# I2C16RJ45.net
KiCad netlist of a schematic drawn in EAGLE
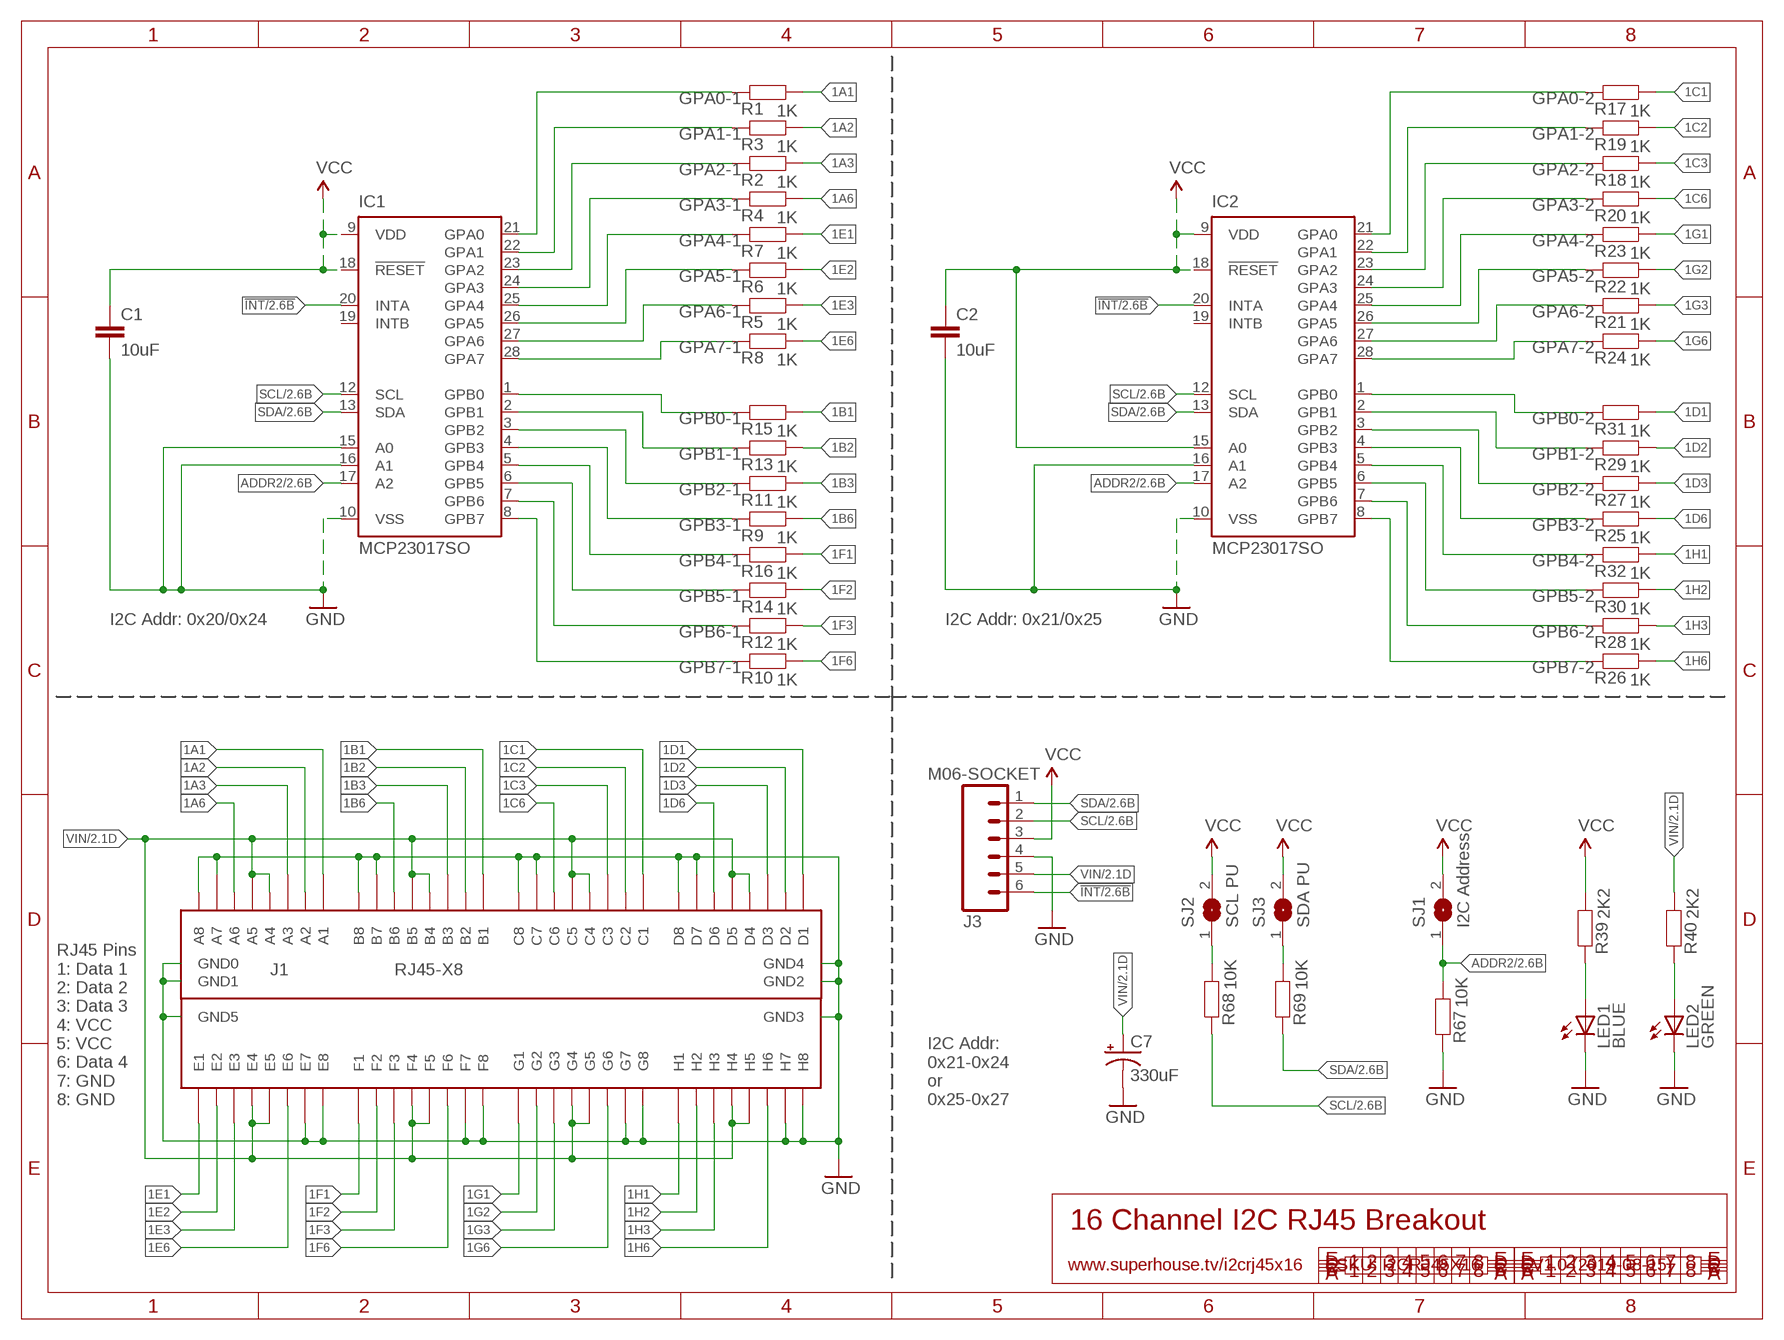
[diagram p0: schematic, sheet 1]
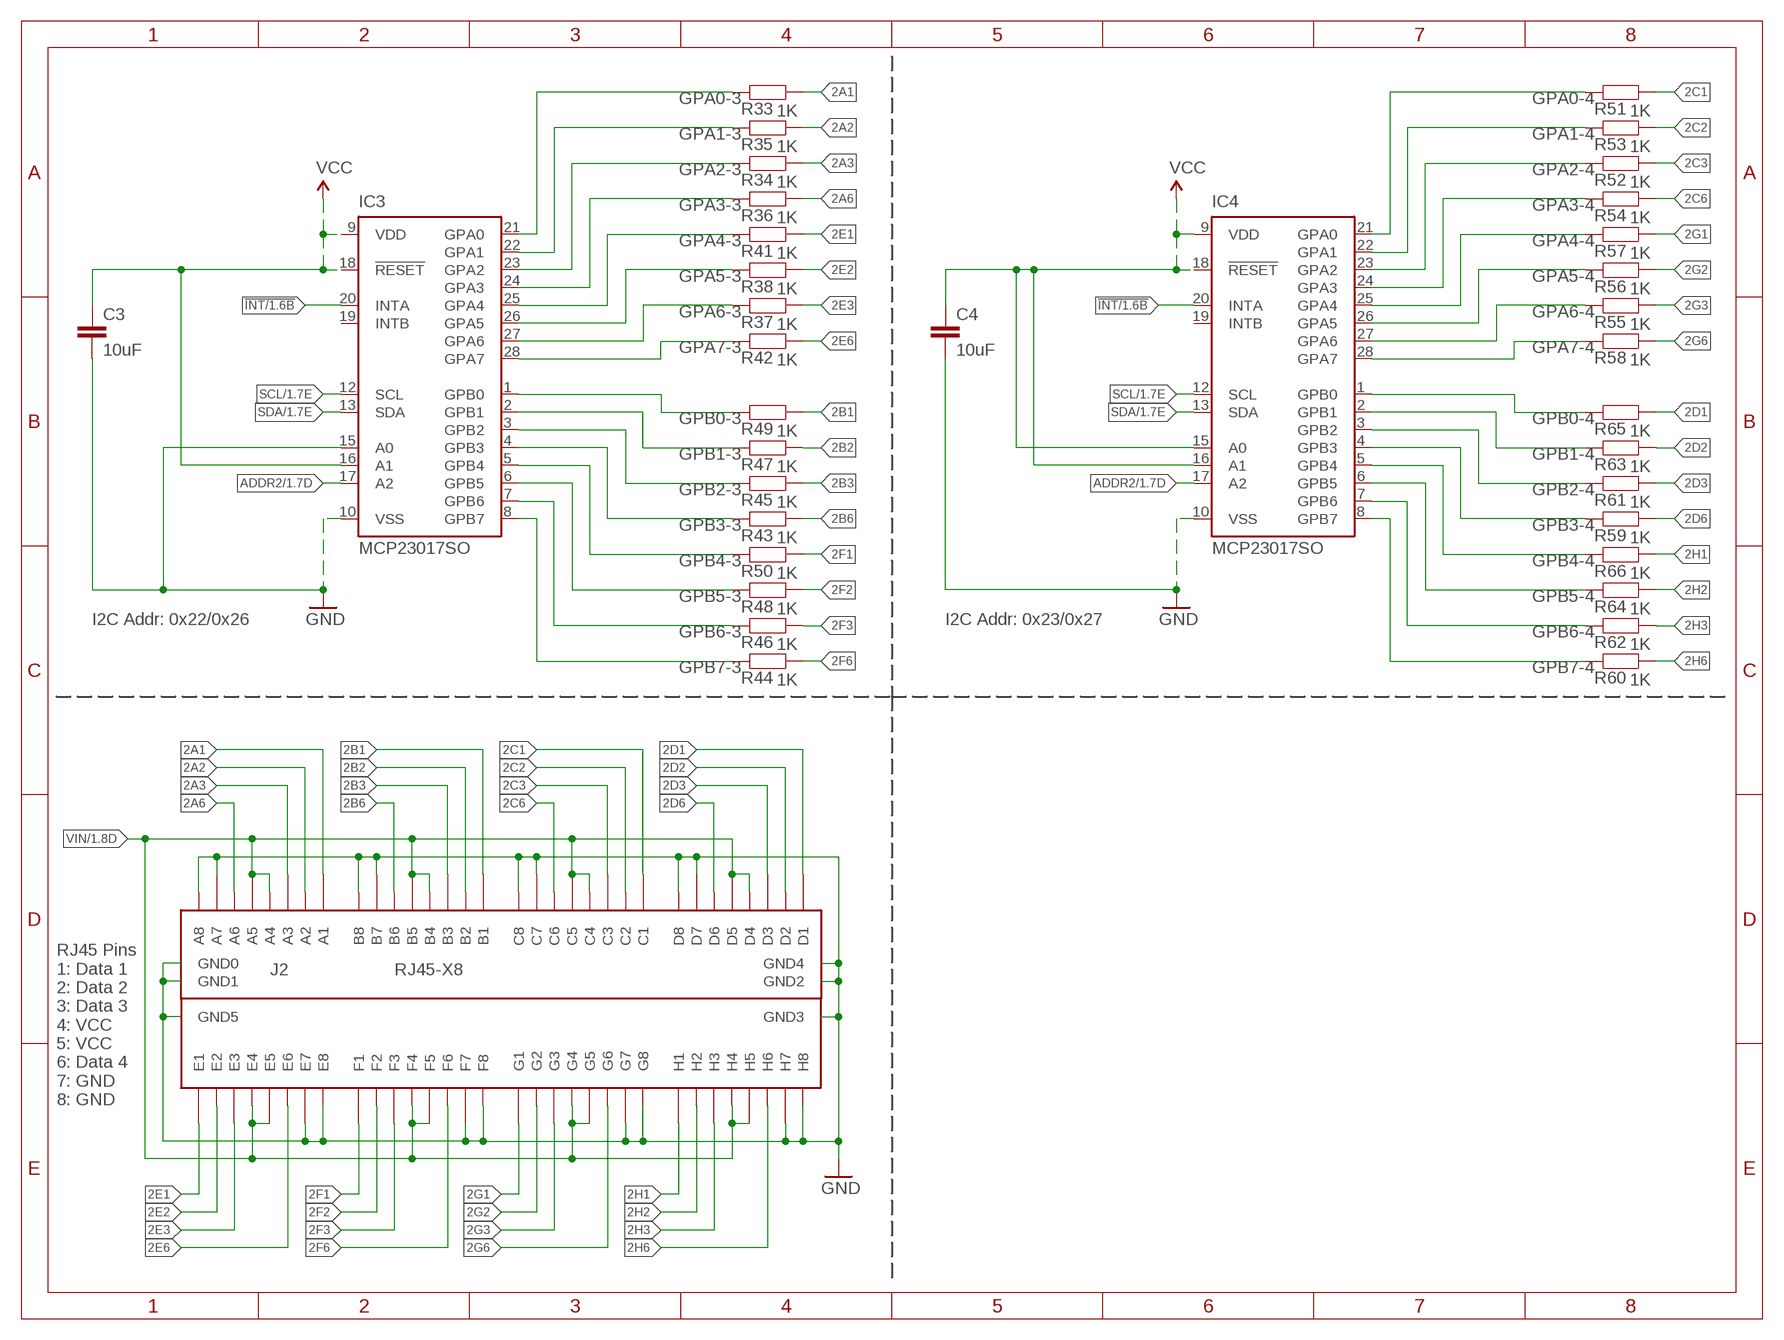
[diagram p1: schematic, sheet 2]

(export (version "E")
  (design (tool "Eeschema 10.0.6"))
  (components
    (comp (ref "C3")
      (value "10uF")
      (footprint "eagle-import:C0805")
      (libsource (lib "eagle-import") (part "CAP0805"))
    )
    (comp (ref "C4")
      (value "10uF")
      (footprint "eagle-import:C0805")
      (libsource (lib "eagle-import") (part "CAP0805"))
    )
    (comp (ref "IC3")
      (value "MCP23017SO")
      (footprint "eagle-import:SO28W")
      (libsource (lib "eagle-import") (part "MCP23017SO"))
    )
    (comp (ref "IC4")
      (value "MCP23017SO")
      (footprint "eagle-import:SO28W")
      (libsource (lib "eagle-import") (part "MCP23017SO"))
    )
    (comp (ref "J2")
      (value "RJ45-X8")
      (footprint "eagle-import:RJ45-2X4")
      (libsource (lib "eagle-import") (part "RJ45-X8"))
    )
    (comp (ref "R33")
      (value "1K")
      (footprint "eagle-import:R0603")
      (libsource (lib "eagle-import") (part "RESISTOR0603"))
    )
    (comp (ref "R34")
      (value "1K")
      (footprint "eagle-import:R0603")
      (libsource (lib "eagle-import") (part "RESISTOR0603"))
    )
    (comp (ref "R35")
      (value "1K")
      (footprint "eagle-import:R0603")
      (libsource (lib "eagle-import") (part "RESISTOR0603"))
    )
    (comp (ref "R36")
      (value "1K")
      (footprint "eagle-import:R0603")
      (libsource (lib "eagle-import") (part "RESISTOR0603"))
    )
    (comp (ref "R37")
      (value "1K")
      (footprint "eagle-import:R0603")
      (libsource (lib "eagle-import") (part "RESISTOR0603"))
    )
    (comp (ref "R38")
      (value "1K")
      (footprint "eagle-import:R0603")
      (libsource (lib "eagle-import") (part "RESISTOR0603"))
    )
    (comp (ref "R41")
      (value "1K")
      (footprint "eagle-import:R0603")
      (libsource (lib "eagle-import") (part "RESISTOR0603"))
    )
    (comp (ref "R42")
      (value "1K")
      (footprint "eagle-import:R0603")
      (libsource (lib "eagle-import") (part "RESISTOR0603"))
    )
    (comp (ref "R43")
      (value "1K")
      (footprint "eagle-import:R0603")
      (libsource (lib "eagle-import") (part "RESISTOR0603"))
    )
    (comp (ref "R44")
      (value "1K")
      (footprint "eagle-import:R0603")
      (libsource (lib "eagle-import") (part "RESISTOR0603"))
    )
    (comp (ref "R45")
      (value "1K")
      (footprint "eagle-import:R0603")
      (libsource (lib "eagle-import") (part "RESISTOR0603"))
    )
    (comp (ref "R46")
      (value "1K")
      (footprint "eagle-import:R0603")
      (libsource (lib "eagle-import") (part "RESISTOR0603"))
    )
    (comp (ref "R47")
      (value "1K")
      (footprint "eagle-import:R0603")
      (libsource (lib "eagle-import") (part "RESISTOR0603"))
    )
    (comp (ref "R48")
      (value "1K")
      (footprint "eagle-import:R0603")
      (libsource (lib "eagle-import") (part "RESISTOR0603"))
    )
    (comp (ref "R49")
      (value "1K")
      (footprint "eagle-import:R0603")
      (libsource (lib "eagle-import") (part "RESISTOR0603"))
    )
    (comp (ref "R50")
      (value "1K")
      (footprint "eagle-import:R0603")
      (libsource (lib "eagle-import") (part "RESISTOR0603"))
    )
    (comp (ref "R51")
      (value "1K")
      (footprint "eagle-import:R0603")
      (libsource (lib "eagle-import") (part "RESISTOR0603"))
    )
    (comp (ref "R52")
      (value "1K")
      (footprint "eagle-import:R0603")
      (libsource (lib "eagle-import") (part "RESISTOR0603"))
    )
    (comp (ref "R53")
      (value "1K")
      (footprint "eagle-import:R0603")
      (libsource (lib "eagle-import") (part "RESISTOR0603"))
    )
    (comp (ref "R54")
      (value "1K")
      (footprint "eagle-import:R0603")
      (libsource (lib "eagle-import") (part "RESISTOR0603"))
    )
    (comp (ref "R55")
      (value "1K")
      (footprint "eagle-import:R0603")
      (libsource (lib "eagle-import") (part "RESISTOR0603"))
    )
    (comp (ref "R56")
      (value "1K")
      (footprint "eagle-import:R0603")
      (libsource (lib "eagle-import") (part "RESISTOR0603"))
    )
    (comp (ref "R57")
      (value "1K")
      (footprint "eagle-import:R0603")
      (libsource (lib "eagle-import") (part "RESISTOR0603"))
    )
    (comp (ref "R58")
      (value "1K")
      (footprint "eagle-import:R0603")
      (libsource (lib "eagle-import") (part "RESISTOR0603"))
    )
    (comp (ref "R59")
      (value "1K")
      (footprint "eagle-import:R0603")
      (libsource (lib "eagle-import") (part "RESISTOR0603"))
    )
    (comp (ref "R60")
      (value "1K")
      (footprint "eagle-import:R0603")
      (libsource (lib "eagle-import") (part "RESISTOR0603"))
    )
    (comp (ref "R61")
      (value "1K")
      (footprint "eagle-import:R0603")
      (libsource (lib "eagle-import") (part "RESISTOR0603"))
    )
    (comp (ref "R62")
      (value "1K")
      (footprint "eagle-import:R0603")
      (libsource (lib "eagle-import") (part "RESISTOR0603"))
    )
    (comp (ref "R63")
      (value "1K")
      (footprint "eagle-import:R0603")
      (libsource (lib "eagle-import") (part "RESISTOR0603"))
    )
    (comp (ref "R64")
      (value "1K")
      (footprint "eagle-import:R0603")
      (libsource (lib "eagle-import") (part "RESISTOR0603"))
    )
    (comp (ref "R65")
      (value "1K")
      (footprint "eagle-import:R0603")
      (libsource (lib "eagle-import") (part "RESISTOR0603"))
    )
    (comp (ref "R66")
      (value "1K")
      (footprint "eagle-import:R0603")
      (libsource (lib "eagle-import") (part "RESISTOR0603"))
    )
    (comp (ref "C1")
      (value "10uF")
      (footprint "eagle-import:C0805")
      (libsource (lib "eagle-import") (part "CAP0805"))
    )
    (comp (ref "C2")
      (value "10uF")
      (footprint "eagle-import:C0805")
      (libsource (lib "eagle-import") (part "CAP0805"))
    )
    (comp (ref "C7")
      (value "330uF")
      (footprint "eagle-import:PANASONIC_G")
      (libsource (lib "eagle-import") (part "CAP_POLG"))
    )
    (comp (ref "IC1")
      (value "MCP23017SO")
      (footprint "eagle-import:SO28W")
      (libsource (lib "eagle-import") (part "MCP23017SO"))
    )
    (comp (ref "IC2")
      (value "MCP23017SO")
      (footprint "eagle-import:SO28W")
      (libsource (lib "eagle-import") (part "MCP23017SO"))
    )
    (comp (ref "J1")
      (value "RJ45-X8")
      (footprint "eagle-import:RJ45-2X4")
      (libsource (lib "eagle-import") (part "RJ45-X8"))
    )
    (comp (ref "J3")
      (value "M06-SOCKET")
      (footprint "eagle-import:1X06-S")
      (libsource (lib "eagle-import") (part "M06-SOCKET"))
    )
    (comp (ref "LED1")
      (value "BLUE")
      (footprint "eagle-import:LED-0603")
      (libsource (lib "eagle-import") (part "LED0603"))
    )
    (comp (ref "LED2")
      (value "GREEN")
      (footprint "eagle-import:LED-0603")
      (libsource (lib "eagle-import") (part "LED0603"))
    )
    (comp (ref "R1")
      (value "1K")
      (footprint "eagle-import:R0603")
      (libsource (lib "eagle-import") (part "RESISTOR0603"))
    )
    (comp (ref "R2")
      (value "1K")
      (footprint "eagle-import:R0603")
      (libsource (lib "eagle-import") (part "RESISTOR0603"))
    )
    (comp (ref "R3")
      (value "1K")
      (footprint "eagle-import:R0603")
      (libsource (lib "eagle-import") (part "RESISTOR0603"))
    )
    (comp (ref "R4")
      (value "1K")
      (footprint "eagle-import:R0603")
      (libsource (lib "eagle-import") (part "RESISTOR0603"))
    )
    (comp (ref "R5")
      (value "1K")
      (footprint "eagle-import:R0603")
      (libsource (lib "eagle-import") (part "RESISTOR0603"))
    )
    (comp (ref "R6")
      (value "1K")
      (footprint "eagle-import:R0603")
      (libsource (lib "eagle-import") (part "RESISTOR0603"))
    )
    (comp (ref "R7")
      (value "1K")
      (footprint "eagle-import:R0603")
      (libsource (lib "eagle-import") (part "RESISTOR0603"))
    )
    (comp (ref "R8")
      (value "1K")
      (footprint "eagle-import:R0603")
      (libsource (lib "eagle-import") (part "RESISTOR0603"))
    )
    (comp (ref "R9")
      (value "1K")
      (footprint "eagle-import:R0603")
      (libsource (lib "eagle-import") (part "RESISTOR0603"))
    )
    (comp (ref "R10")
      (value "1K")
      (footprint "eagle-import:R0603")
      (libsource (lib "eagle-import") (part "RESISTOR0603"))
    )
    (comp (ref "R11")
      (value "1K")
      (footprint "eagle-import:R0603")
      (libsource (lib "eagle-import") (part "RESISTOR0603"))
    )
    (comp (ref "R12")
      (value "1K")
      (footprint "eagle-import:R0603")
      (libsource (lib "eagle-import") (part "RESISTOR0603"))
    )
    (comp (ref "R13")
      (value "1K")
      (footprint "eagle-import:R0603")
      (libsource (lib "eagle-import") (part "RESISTOR0603"))
    )
    (comp (ref "R14")
      (value "1K")
      (footprint "eagle-import:R0603")
      (libsource (lib "eagle-import") (part "RESISTOR0603"))
    )
    (comp (ref "R15")
      (value "1K")
      (footprint "eagle-import:R0603")
      (libsource (lib "eagle-import") (part "RESISTOR0603"))
    )
    (comp (ref "R16")
      (value "1K")
      (footprint "eagle-import:R0603")
      (libsource (lib "eagle-import") (part "RESISTOR0603"))
    )
    (comp (ref "R17")
      (value "1K")
      (footprint "eagle-import:R0603")
      (libsource (lib "eagle-import") (part "RESISTOR0603"))
    )
    (comp (ref "R18")
      (value "1K")
      (footprint "eagle-import:R0603")
      (libsource (lib "eagle-import") (part "RESISTOR0603"))
    )
    (comp (ref "R19")
      (value "1K")
      (footprint "eagle-import:R0603")
      (libsource (lib "eagle-import") (part "RESISTOR0603"))
    )
    (comp (ref "R20")
      (value "1K")
      (footprint "eagle-import:R0603")
      (libsource (lib "eagle-import") (part "RESISTOR0603"))
    )
    (comp (ref "R21")
      (value "1K")
      (footprint "eagle-import:R0603")
      (libsource (lib "eagle-import") (part "RESISTOR0603"))
    )
    (comp (ref "R22")
      (value "1K")
      (footprint "eagle-import:R0603")
      (libsource (lib "eagle-import") (part "RESISTOR0603"))
    )
    (comp (ref "R23")
      (value "1K")
      (footprint "eagle-import:R0603")
      (libsource (lib "eagle-import") (part "RESISTOR0603"))
    )
    (comp (ref "R24")
      (value "1K")
      (footprint "eagle-import:R0603")
      (libsource (lib "eagle-import") (part "RESISTOR0603"))
    )
    (comp (ref "R25")
      (value "1K")
      (footprint "eagle-import:R0603")
      (libsource (lib "eagle-import") (part "RESISTOR0603"))
    )
    (comp (ref "R26")
      (value "1K")
      (footprint "eagle-import:R0603")
      (libsource (lib "eagle-import") (part "RESISTOR0603"))
    )
    (comp (ref "R27")
      (value "1K")
      (footprint "eagle-import:R0603")
      (libsource (lib "eagle-import") (part "RESISTOR0603"))
    )
    (comp (ref "R28")
      (value "1K")
      (footprint "eagle-import:R0603")
      (libsource (lib "eagle-import") (part "RESISTOR0603"))
    )
    (comp (ref "R29")
      (value "1K")
      (footprint "eagle-import:R0603")
      (libsource (lib "eagle-import") (part "RESISTOR0603"))
    )
    (comp (ref "R30")
      (value "1K")
      (footprint "eagle-import:R0603")
      (libsource (lib "eagle-import") (part "RESISTOR0603"))
    )
    (comp (ref "R31")
      (value "1K")
      (footprint "eagle-import:R0603")
      (libsource (lib "eagle-import") (part "RESISTOR0603"))
    )
    (comp (ref "R32")
      (value "1K")
      (footprint "eagle-import:R0603")
      (libsource (lib "eagle-import") (part "RESISTOR0603"))
    )
    (comp (ref "R39")
      (value "2K2")
      (footprint "eagle-import:R0603")
      (libsource (lib "eagle-import") (part "RESISTOR0603"))
    )
    (comp (ref "R40")
      (value "2K2")
      (footprint "eagle-import:R0603")
      (libsource (lib "eagle-import") (part "RESISTOR0603"))
    )
    (comp (ref "R67")
      (value "10K")
      (footprint "eagle-import:R0603")
      (libsource (lib "eagle-import") (part "RESISTOR0603"))
    )
    (comp (ref "R68")
      (value "10K")
      (footprint "eagle-import:R0603")
      (libsource (lib "eagle-import") (part "RESISTOR0603"))
    )
    (comp (ref "R69")
      (value "10K")
      (footprint "eagle-import:R0603")
      (libsource (lib "eagle-import") (part "RESISTOR0603"))
    )
    (comp (ref "SJ1")
      (value "I2C Address")
      (footprint "eagle-import:SJ")
      (libsource (lib "eagle-import") (part "SJ-NORMAL"))
    )
    (comp (ref "SJ2")
      (value "SCL PU")
      (footprint "eagle-import:SJ")
      (libsource (lib "eagle-import") (part "SJ-NORMAL"))
    )
    (comp (ref "SJ3")
      (value "SDA PU")
      (footprint "eagle-import:SJ")
      (libsource (lib "eagle-import") (part "SJ-NORMAL"))
    )
  )
  (nets
    (net (code "1") (name "1A1") (class "Default")
      (node (ref "J1") (pin "A1") (pinfunction "A1_A1") (pintype "bidirectional"))
      (node (ref "R1") (pin "2") (pinfunction "2_2") (pintype "passive"))
    )
    (net (code "2") (name "1A2") (class "Default")
      (node (ref "J1") (pin "A2") (pinfunction "A2_A2") (pintype "bidirectional"))
      (node (ref "R3") (pin "2") (pinfunction "2_2") (pintype "passive"))
    )
    (net (code "3") (name "1A3") (class "Default")
      (node (ref "J1") (pin "A3") (pinfunction "A3_A3") (pintype "bidirectional"))
      (node (ref "R2") (pin "2") (pinfunction "2_2") (pintype "passive"))
    )
    (net (code "4") (name "1A6") (class "Default")
      (node (ref "J1") (pin "A6") (pinfunction "A6_A6") (pintype "bidirectional"))
      (node (ref "R4") (pin "2") (pinfunction "2_2") (pintype "passive"))
    )
    (net (code "5") (name "1B1") (class "Default")
      (node (ref "J1") (pin "B1") (pinfunction "B1_B1") (pintype "bidirectional"))
      (node (ref "R15") (pin "2") (pinfunction "2_2") (pintype "passive"))
    )
    (net (code "6") (name "1B2") (class "Default")
      (node (ref "J1") (pin "B2") (pinfunction "B2_B2") (pintype "bidirectional"))
      (node (ref "R13") (pin "2") (pinfunction "2_2") (pintype "passive"))
    )
    (net (code "7") (name "1B3") (class "Default")
      (node (ref "J1") (pin "B3") (pinfunction "B3_B3") (pintype "bidirectional"))
      (node (ref "R11") (pin "2") (pinfunction "2_2") (pintype "passive"))
    )
    (net (code "8") (name "1B6") (class "Default")
      (node (ref "J1") (pin "B6") (pinfunction "B6_B6") (pintype "bidirectional"))
      (node (ref "R9") (pin "2") (pinfunction "2_2") (pintype "passive"))
    )
    (net (code "9") (name "1C1") (class "Default")
      (node (ref "J1") (pin "C1") (pinfunction "C1_C1") (pintype "bidirectional"))
      (node (ref "R17") (pin "2") (pinfunction "2_2") (pintype "passive"))
    )
    (net (code "10") (name "1C2") (class "Default")
      (node (ref "J1") (pin "C2") (pinfunction "C2_C2") (pintype "bidirectional"))
      (node (ref "R19") (pin "2") (pinfunction "2_2") (pintype "passive"))
    )
    (net (code "11") (name "1C3") (class "Default")
      (node (ref "J1") (pin "C3") (pinfunction "C3_C3") (pintype "bidirectional"))
      (node (ref "R18") (pin "2") (pinfunction "2_2") (pintype "passive"))
    )
    (net (code "12") (name "1C6") (class "Default")
      (node (ref "J1") (pin "C6") (pinfunction "C6_C6") (pintype "bidirectional"))
      (node (ref "R20") (pin "2") (pinfunction "2_2") (pintype "passive"))
    )
    (net (code "13") (name "1D1") (class "Default")
      (node (ref "J1") (pin "D1") (pinfunction "D1_D1") (pintype "bidirectional"))
      (node (ref "R31") (pin "2") (pinfunction "2_2") (pintype "passive"))
    )
    (net (code "14") (name "1D2") (class "Default")
      (node (ref "J1") (pin "D2") (pinfunction "D2_D2") (pintype "bidirectional"))
      (node (ref "R29") (pin "2") (pinfunction "2_2") (pintype "passive"))
    )
    (net (code "15") (name "1D3") (class "Default")
      (node (ref "J1") (pin "D3") (pinfunction "D3_D3") (pintype "bidirectional"))
      (node (ref "R27") (pin "2") (pinfunction "2_2") (pintype "passive"))
    )
    (net (code "16") (name "1D6") (class "Default")
      (node (ref "J1") (pin "D6") (pinfunction "D6_D6") (pintype "bidirectional"))
      (node (ref "R25") (pin "2") (pinfunction "2_2") (pintype "passive"))
    )
    (net (code "17") (name "1E1") (class "Default")
      (node (ref "J1") (pin "E1") (pinfunction "E1_E1") (pintype "bidirectional"))
      (node (ref "R7") (pin "2") (pinfunction "2_2") (pintype "passive"))
    )
    (net (code "18") (name "1E2") (class "Default")
      (node (ref "J1") (pin "E2") (pinfunction "E2_E2") (pintype "bidirectional"))
      (node (ref "R6") (pin "2") (pinfunction "2_2") (pintype "passive"))
    )
    (net (code "19") (name "1E3") (class "Default")
      (node (ref "J1") (pin "E3") (pinfunction "E3_E3") (pintype "bidirectional"))
      (node (ref "R5") (pin "2") (pinfunction "2_2") (pintype "passive"))
    )
    (net (code "20") (name "1E6") (class "Default")
      (node (ref "J1") (pin "E6") (pinfunction "E6_E6") (pintype "bidirectional"))
      (node (ref "R8") (pin "2") (pinfunction "2_2") (pintype "passive"))
    )
    (net (code "21") (name "1F1") (class "Default")
      (node (ref "J1") (pin "F1") (pinfunction "F1_F1") (pintype "bidirectional"))
      (node (ref "R16") (pin "2") (pinfunction "2_2") (pintype "passive"))
    )
    (net (code "22") (name "1F2") (class "Default")
      (node (ref "J1") (pin "F2") (pinfunction "F2_F2") (pintype "bidirectional"))
      (node (ref "R14") (pin "2") (pinfunction "2_2") (pintype "passive"))
    )
    (net (code "23") (name "1F3") (class "Default")
      (node (ref "J1") (pin "F3") (pinfunction "F3_F3") (pintype "bidirectional"))
      (node (ref "R12") (pin "2") (pinfunction "2_2") (pintype "passive"))
    )
    (net (code "24") (name "1F6") (class "Default")
      (node (ref "J1") (pin "F6") (pinfunction "F6_F6") (pintype "bidirectional"))
      (node (ref "R10") (pin "2") (pinfunction "2_2") (pintype "passive"))
    )
    (net (code "25") (name "1G1") (class "Default")
      (node (ref "J1") (pin "G1") (pinfunction "G1_G1") (pintype "bidirectional"))
      (node (ref "R23") (pin "2") (pinfunction "2_2") (pintype "passive"))
    )
    (net (code "26") (name "1G2") (class "Default")
      (node (ref "J1") (pin "G2") (pinfunction "G2_G2") (pintype "bidirectional"))
      (node (ref "R22") (pin "2") (pinfunction "2_2") (pintype "passive"))
    )
    (net (code "27") (name "1G3") (class "Default")
      (node (ref "J1") (pin "G3") (pinfunction "G3_G3") (pintype "bidirectional"))
      (node (ref "R21") (pin "2") (pinfunction "2_2") (pintype "passive"))
    )
    (net (code "28") (name "1G6") (class "Default")
      (node (ref "J1") (pin "G6") (pinfunction "G6_G6") (pintype "bidirectional"))
      (node (ref "R24") (pin "2") (pinfunction "2_2") (pintype "passive"))
    )
    (net (code "29") (name "1H1") (class "Default")
      (node (ref "J1") (pin "H1") (pinfunction "H1_H1") (pintype "bidirectional"))
      (node (ref "R32") (pin "2") (pinfunction "2_2") (pintype "passive"))
    )
    (net (code "30") (name "1H2") (class "Default")
      (node (ref "J1") (pin "H2") (pinfunction "H2_H2") (pintype "bidirectional"))
      (node (ref "R30") (pin "2") (pinfunction "2_2") (pintype "passive"))
    )
    (net (code "31") (name "1H3") (class "Default")
      (node (ref "J1") (pin "H3") (pinfunction "H3_H3") (pintype "bidirectional"))
      (node (ref "R28") (pin "2") (pinfunction "2_2") (pintype "passive"))
    )
    (net (code "32") (name "1H6") (class "Default")
      (node (ref "J1") (pin "H6") (pinfunction "H6_H6") (pintype "bidirectional"))
      (node (ref "R26") (pin "2") (pinfunction "2_2") (pintype "passive"))
    )
    (net (code "33") (name "2A1") (class "Default")
      (node (ref "J2") (pin "A1") (pinfunction "A1_A1") (pintype "bidirectional"))
      (node (ref "R33") (pin "2") (pinfunction "2_2") (pintype "passive"))
    )
    (net (code "34") (name "2A2") (class "Default")
      (node (ref "J2") (pin "A2") (pinfunction "A2_A2") (pintype "bidirectional"))
      (node (ref "R35") (pin "2") (pinfunction "2_2") (pintype "passive"))
    )
    (net (code "35") (name "2A3") (class "Default")
      (node (ref "J2") (pin "A3") (pinfunction "A3_A3") (pintype "bidirectional"))
      (node (ref "R34") (pin "2") (pinfunction "2_2") (pintype "passive"))
    )
    (net (code "36") (name "2A6") (class "Default")
      (node (ref "J2") (pin "A6") (pinfunction "A6_A6") (pintype "bidirectional"))
      (node (ref "R36") (pin "2") (pinfunction "2_2") (pintype "passive"))
    )
    (net (code "37") (name "2B1") (class "Default")
      (node (ref "J2") (pin "B1") (pinfunction "B1_B1") (pintype "bidirectional"))
      (node (ref "R49") (pin "2") (pinfunction "2_2") (pintype "passive"))
    )
    (net (code "38") (name "2B2") (class "Default")
      (node (ref "J2") (pin "B2") (pinfunction "B2_B2") (pintype "bidirectional"))
      (node (ref "R47") (pin "2") (pinfunction "2_2") (pintype "passive"))
    )
    (net (code "39") (name "2B3") (class "Default")
      (node (ref "J2") (pin "B3") (pinfunction "B3_B3") (pintype "bidirectional"))
      (node (ref "R45") (pin "2") (pinfunction "2_2") (pintype "passive"))
    )
    (net (code "40") (name "2B6") (class "Default")
      (node (ref "J2") (pin "B6") (pinfunction "B6_B6") (pintype "bidirectional"))
      (node (ref "R43") (pin "2") (pinfunction "2_2") (pintype "passive"))
    )
    (net (code "41") (name "2C1") (class "Default")
      (node (ref "J2") (pin "C1") (pinfunction "C1_C1") (pintype "bidirectional"))
      (node (ref "R51") (pin "2") (pinfunction "2_2") (pintype "passive"))
    )
    (net (code "42") (name "2C2") (class "Default")
      (node (ref "J2") (pin "C2") (pinfunction "C2_C2") (pintype "bidirectional"))
      (node (ref "R53") (pin "2") (pinfunction "2_2") (pintype "passive"))
    )
    (net (code "43") (name "2C3") (class "Default")
      (node (ref "J2") (pin "C3") (pinfunction "C3_C3") (pintype "bidirectional"))
      (node (ref "R52") (pin "2") (pinfunction "2_2") (pintype "passive"))
    )
    (net (code "44") (name "2C6") (class "Default")
      (node (ref "J2") (pin "C6") (pinfunction "C6_C6") (pintype "bidirectional"))
      (node (ref "R54") (pin "2") (pinfunction "2_2") (pintype "passive"))
    )
    (net (code "45") (name "2D1") (class "Default")
      (node (ref "J2") (pin "D1") (pinfunction "D1_D1") (pintype "bidirectional"))
      (node (ref "R65") (pin "2") (pinfunction "2_2") (pintype "passive"))
    )
    (net (code "46") (name "2D2") (class "Default")
      (node (ref "J2") (pin "D2") (pinfunction "D2_D2") (pintype "bidirectional"))
      (node (ref "R63") (pin "2") (pinfunction "2_2") (pintype "passive"))
    )
    (net (code "47") (name "2D3") (class "Default")
      (node (ref "J2") (pin "D3") (pinfunction "D3_D3") (pintype "bidirectional"))
      (node (ref "R61") (pin "2") (pinfunction "2_2") (pintype "passive"))
    )
    (net (code "48") (name "2D6") (class "Default")
      (node (ref "J2") (pin "D6") (pinfunction "D6_D6") (pintype "bidirectional"))
      (node (ref "R59") (pin "2") (pinfunction "2_2") (pintype "passive"))
    )
    (net (code "49") (name "2E1") (class "Default")
      (node (ref "J2") (pin "E1") (pinfunction "E1_E1") (pintype "bidirectional"))
      (node (ref "R41") (pin "2") (pinfunction "2_2") (pintype "passive"))
    )
    (net (code "50") (name "2E2") (class "Default")
      (node (ref "J2") (pin "E2") (pinfunction "E2_E2") (pintype "bidirectional"))
      (node (ref "R38") (pin "2") (pinfunction "2_2") (pintype "passive"))
    )
    (net (code "51") (name "2E3") (class "Default")
      (node (ref "J2") (pin "E3") (pinfunction "E3_E3") (pintype "bidirectional"))
      (node (ref "R37") (pin "2") (pinfunction "2_2") (pintype "passive"))
    )
    (net (code "52") (name "2E6") (class "Default")
      (node (ref "J2") (pin "E6") (pinfunction "E6_E6") (pintype "bidirectional"))
      (node (ref "R42") (pin "2") (pinfunction "2_2") (pintype "passive"))
    )
    (net (code "53") (name "2F1") (class "Default")
      (node (ref "J2") (pin "F1") (pinfunction "F1_F1") (pintype "bidirectional"))
      (node (ref "R50") (pin "2") (pinfunction "2_2") (pintype "passive"))
    )
    (net (code "54") (name "2F2") (class "Default")
      (node (ref "J2") (pin "F2") (pinfunction "F2_F2") (pintype "bidirectional"))
      (node (ref "R48") (pin "2") (pinfunction "2_2") (pintype "passive"))
    )
    (net (code "55") (name "2F3") (class "Default")
      (node (ref "J2") (pin "F3") (pinfunction "F3_F3") (pintype "bidirectional"))
      (node (ref "R46") (pin "2") (pinfunction "2_2") (pintype "passive"))
    )
    (net (code "56") (name "2F6") (class "Default")
      (node (ref "J2") (pin "F6") (pinfunction "F6_F6") (pintype "bidirectional"))
      (node (ref "R44") (pin "2") (pinfunction "2_2") (pintype "passive"))
    )
    (net (code "57") (name "2G1") (class "Default")
      (node (ref "J2") (pin "G1") (pinfunction "G1_G1") (pintype "bidirectional"))
      (node (ref "R57") (pin "2") (pinfunction "2_2") (pintype "passive"))
    )
    (net (code "58") (name "2G2") (class "Default")
      (node (ref "J2") (pin "G2") (pinfunction "G2_G2") (pintype "bidirectional"))
      (node (ref "R56") (pin "2") (pinfunction "2_2") (pintype "passive"))
    )
    (net (code "59") (name "2G3") (class "Default")
      (node (ref "J2") (pin "G3") (pinfunction "G3_G3") (pintype "bidirectional"))
      (node (ref "R55") (pin "2") (pinfunction "2_2") (pintype "passive"))
    )
    (net (code "60") (name "2G6") (class "Default")
      (node (ref "J2") (pin "G6") (pinfunction "G6_G6") (pintype "bidirectional"))
      (node (ref "R58") (pin "2") (pinfunction "2_2") (pintype "passive"))
    )
    (net (code "61") (name "2H1") (class "Default")
      (node (ref "J2") (pin "H1") (pinfunction "H1_H1") (pintype "bidirectional"))
      (node (ref "R66") (pin "2") (pinfunction "2_2") (pintype "passive"))
    )
    (net (code "62") (name "2H2") (class "Default")
      (node (ref "J2") (pin "H2") (pinfunction "H2_H2") (pintype "bidirectional"))
      (node (ref "R64") (pin "2") (pinfunction "2_2") (pintype "passive"))
    )
    (net (code "63") (name "2H3") (class "Default")
      (node (ref "J2") (pin "H3") (pinfunction "H3_H3") (pintype "bidirectional"))
      (node (ref "R62") (pin "2") (pinfunction "2_2") (pintype "passive"))
    )
    (net (code "64") (name "2H6") (class "Default")
      (node (ref "J2") (pin "H6") (pinfunction "H6_H6") (pintype "bidirectional"))
      (node (ref "R60") (pin "2") (pinfunction "2_2") (pintype "passive"))
    )
    (net (code "65") (name "ADDR2") (class "Default")
      (node (ref "IC1") (pin "17") (pinfunction "A2_17") (pintype "input"))
      (node (ref "IC2") (pin "17") (pinfunction "A2_17") (pintype "input"))
      (node (ref "IC3") (pin "17") (pinfunction "A2_17") (pintype "input"))
      (node (ref "IC4") (pin "17") (pinfunction "A2_17") (pintype "input"))
      (node (ref "R67") (pin "2") (pinfunction "2_2") (pintype "passive"))
      (node (ref "SJ1") (pin "1") (pinfunction "1_1") (pintype "passive"))
    )
    (net (code "66") (name "GND") (class "Default")
      (node (ref "C1") (pin "2") (pinfunction "2_2") (pintype "passive"))
      (node (ref "C2") (pin "2") (pinfunction "2_2") (pintype "passive"))
      (node (ref "C3") (pin "2") (pinfunction "2_2") (pintype "passive"))
      (node (ref "C4") (pin "2") (pinfunction "2_2") (pintype "passive"))
      (node (ref "C7") (pin "-") (pinfunction "-_-") (pintype "passive"))
      (node (ref "IC1") (pin "10") (pinfunction "VSS_10") (pintype "power_in"))
      (node (ref "IC1") (pin "15") (pinfunction "A0_15") (pintype "input"))
      (node (ref "IC1") (pin "16") (pinfunction "A1_16") (pintype "input"))
      (node (ref "IC2") (pin "10") (pinfunction "VSS_10") (pintype "power_in"))
      (node (ref "IC2") (pin "16") (pinfunction "A1_16") (pintype "input"))
      (node (ref "IC3") (pin "10") (pinfunction "VSS_10") (pintype "power_in"))
      (node (ref "IC3") (pin "15") (pinfunction "A0_15") (pintype "input"))
      (node (ref "IC4") (pin "10") (pinfunction "VSS_10") (pintype "power_in"))
      (node (ref "J1") (pin "A7") (pinfunction "A7_A7") (pintype "bidirectional"))
      (node (ref "J1") (pin "A8") (pinfunction "A8_A8") (pintype "bidirectional"))
      (node (ref "J1") (pin "B7") (pinfunction "B7_B7") (pintype "bidirectional"))
      (node (ref "J1") (pin "B8") (pinfunction "B8_B8") (pintype "bidirectional"))
      (node (ref "J1") (pin "C7") (pinfunction "C7_C7") (pintype "bidirectional"))
      (node (ref "J1") (pin "C8") (pinfunction "C8_C8") (pintype "bidirectional"))
      (node (ref "J1") (pin "D7") (pinfunction "D7_D7") (pintype "bidirectional"))
      (node (ref "J1") (pin "D8") (pinfunction "D8_D8") (pintype "bidirectional"))
      (node (ref "J1") (pin "E7") (pinfunction "E7_E7") (pintype "bidirectional"))
      (node (ref "J1") (pin "E8") (pinfunction "E8_E8") (pintype "bidirectional"))
      (node (ref "J1") (pin "F7") (pinfunction "F7_F7") (pintype "bidirectional"))
      (node (ref "J1") (pin "F8") (pinfunction "F8_F8") (pintype "bidirectional"))
      (node (ref "J1") (pin "G7") (pinfunction "G7_G7") (pintype "bidirectional"))
      (node (ref "J1") (pin "G8") (pinfunction "G8_G8") (pintype "bidirectional"))
      (node (ref "J1") (pin "GND0") (pinfunction "GND0_GND0") (pintype "power_in"))
      (node (ref "J1") (pin "GND1") (pinfunction "GND1_GND1") (pintype "power_in"))
      (node (ref "J1") (pin "GND2") (pinfunction "GND2_GND2") (pintype "power_in"))
      (node (ref "J1") (pin "GND3") (pinfunction "GND3_GND3") (pintype "power_in"))
      (node (ref "J1") (pin "GND4") (pinfunction "GND4_GND4") (pintype "power_in"))
      (node (ref "J1") (pin "GND5") (pinfunction "GND5_GND5") (pintype "power_in"))
      (node (ref "J1") (pin "H7") (pinfunction "H7_H7") (pintype "bidirectional"))
      (node (ref "J1") (pin "H8") (pinfunction "H8_H8") (pintype "bidirectional"))
      (node (ref "J2") (pin "A7") (pinfunction "A7_A7") (pintype "bidirectional"))
      (node (ref "J2") (pin "A8") (pinfunction "A8_A8") (pintype "bidirectional"))
      (node (ref "J2") (pin "B7") (pinfunction "B7_B7") (pintype "bidirectional"))
      (node (ref "J2") (pin "B8") (pinfunction "B8_B8") (pintype "bidirectional"))
      (node (ref "J2") (pin "C7") (pinfunction "C7_C7") (pintype "bidirectional"))
      (node (ref "J2") (pin "C8") (pinfunction "C8_C8") (pintype "bidirectional"))
      (node (ref "J2") (pin "D7") (pinfunction "D7_D7") (pintype "bidirectional"))
      (node (ref "J2") (pin "D8") (pinfunction "D8_D8") (pintype "bidirectional"))
      (node (ref "J2") (pin "E7") (pinfunction "E7_E7") (pintype "bidirectional"))
      (node (ref "J2") (pin "E8") (pinfunction "E8_E8") (pintype "bidirectional"))
      (node (ref "J2") (pin "F7") (pinfunction "F7_F7") (pintype "bidirectional"))
      (node (ref "J2") (pin "F8") (pinfunction "F8_F8") (pintype "bidirectional"))
      (node (ref "J2") (pin "G7") (pinfunction "G7_G7") (pintype "bidirectional"))
      (node (ref "J2") (pin "G8") (pinfunction "G8_G8") (pintype "bidirectional"))
      (node (ref "J2") (pin "GND0") (pinfunction "GND0_GND0") (pintype "power_in"))
      (node (ref "J2") (pin "GND1") (pinfunction "GND1_GND1") (pintype "power_in"))
      (node (ref "J2") (pin "GND2") (pinfunction "GND2_GND2") (pintype "power_in"))
      (node (ref "J2") (pin "GND3") (pinfunction "GND3_GND3") (pintype "power_in"))
      (node (ref "J2") (pin "GND4") (pinfunction "GND4_GND4") (pintype "power_in"))
      (node (ref "J2") (pin "GND5") (pinfunction "GND5_GND5") (pintype "power_in"))
      (node (ref "J2") (pin "H7") (pinfunction "H7_H7") (pintype "bidirectional"))
      (node (ref "J2") (pin "H8") (pinfunction "H8_H8") (pintype "bidirectional"))
      (node (ref "J3") (pin "4") (pinfunction "4_4") (pintype "passive"))
      (node (ref "LED1") (pin "C") (pinfunction "C_C") (pintype "passive"))
      (node (ref "LED2") (pin "C") (pinfunction "C_C") (pintype "passive"))
      (node (ref "R67") (pin "1") (pinfunction "1_1") (pintype "passive"))
    )
    (net (code "67") (name "GPA0-1") (class "Default")
      (node (ref "IC1") (pin "21") (pinfunction "GPA0_21") (pintype "bidirectional"))
      (node (ref "R1") (pin "1") (pinfunction "1_1") (pintype "passive"))
    )
    (net (code "68") (name "GPA0-2") (class "Default")
      (node (ref "IC2") (pin "21") (pinfunction "GPA0_21") (pintype "bidirectional"))
      (node (ref "R17") (pin "1") (pinfunction "1_1") (pintype "passive"))
    )
    (net (code "69") (name "GPA0-3") (class "Default")
      (node (ref "IC3") (pin "21") (pinfunction "GPA0_21") (pintype "bidirectional"))
      (node (ref "R33") (pin "1") (pinfunction "1_1") (pintype "passive"))
    )
    (net (code "70") (name "GPA0-4") (class "Default")
      (node (ref "IC4") (pin "21") (pinfunction "GPA0_21") (pintype "bidirectional"))
      (node (ref "R51") (pin "1") (pinfunction "1_1") (pintype "passive"))
    )
    (net (code "71") (name "GPA1-1") (class "Default")
      (node (ref "IC1") (pin "22") (pinfunction "GPA1_22") (pintype "bidirectional"))
      (node (ref "R3") (pin "1") (pinfunction "1_1") (pintype "passive"))
    )
    (net (code "72") (name "GPA1-2") (class "Default")
      (node (ref "IC2") (pin "22") (pinfunction "GPA1_22") (pintype "bidirectional"))
      (node (ref "R19") (pin "1") (pinfunction "1_1") (pintype "passive"))
    )
    (net (code "73") (name "GPA1-3") (class "Default")
      (node (ref "IC3") (pin "22") (pinfunction "GPA1_22") (pintype "bidirectional"))
      (node (ref "R35") (pin "1") (pinfunction "1_1") (pintype "passive"))
    )
    (net (code "74") (name "GPA1-4") (class "Default")
      (node (ref "IC4") (pin "22") (pinfunction "GPA1_22") (pintype "bidirectional"))
      (node (ref "R53") (pin "1") (pinfunction "1_1") (pintype "passive"))
    )
    (net (code "75") (name "GPA2-1") (class "Default")
      (node (ref "IC1") (pin "23") (pinfunction "GPA2_23") (pintype "bidirectional"))
      (node (ref "R2") (pin "1") (pinfunction "1_1") (pintype "passive"))
    )
    (net (code "76") (name "GPA2-2") (class "Default")
      (node (ref "IC2") (pin "23") (pinfunction "GPA2_23") (pintype "bidirectional"))
      (node (ref "R18") (pin "1") (pinfunction "1_1") (pintype "passive"))
    )
    (net (code "77") (name "GPA2-3") (class "Default")
      (node (ref "IC3") (pin "23") (pinfunction "GPA2_23") (pintype "bidirectional"))
      (node (ref "R34") (pin "1") (pinfunction "1_1") (pintype "passive"))
    )
    (net (code "78") (name "GPA2-4") (class "Default")
      (node (ref "IC4") (pin "23") (pinfunction "GPA2_23") (pintype "bidirectional"))
      (node (ref "R52") (pin "1") (pinfunction "1_1") (pintype "passive"))
    )
    (net (code "79") (name "GPA3-1") (class "Default")
      (node (ref "IC1") (pin "24") (pinfunction "GPA3_24") (pintype "bidirectional"))
      (node (ref "R4") (pin "1") (pinfunction "1_1") (pintype "passive"))
    )
    (net (code "80") (name "GPA3-2") (class "Default")
      (node (ref "IC2") (pin "24") (pinfunction "GPA3_24") (pintype "bidirectional"))
      (node (ref "R20") (pin "1") (pinfunction "1_1") (pintype "passive"))
    )
    (net (code "81") (name "GPA3-3") (class "Default")
      (node (ref "IC3") (pin "24") (pinfunction "GPA3_24") (pintype "bidirectional"))
      (node (ref "R36") (pin "1") (pinfunction "1_1") (pintype "passive"))
    )
    (net (code "82") (name "GPA3-4") (class "Default")
      (node (ref "IC4") (pin "24") (pinfunction "GPA3_24") (pintype "bidirectional"))
      (node (ref "R54") (pin "1") (pinfunction "1_1") (pintype "passive"))
    )
    (net (code "83") (name "GPA4-1") (class "Default")
      (node (ref "IC1") (pin "25") (pinfunction "GPA4_25") (pintype "bidirectional"))
      (node (ref "R7") (pin "1") (pinfunction "1_1") (pintype "passive"))
    )
    (net (code "84") (name "GPA4-2") (class "Default")
      (node (ref "IC2") (pin "25") (pinfunction "GPA4_25") (pintype "bidirectional"))
      (node (ref "R23") (pin "1") (pinfunction "1_1") (pintype "passive"))
    )
    (net (code "85") (name "GPA4-3") (class "Default")
      (node (ref "IC3") (pin "25") (pinfunction "GPA4_25") (pintype "bidirectional"))
      (node (ref "R41") (pin "1") (pinfunction "1_1") (pintype "passive"))
    )
    (net (code "86") (name "GPA4-4") (class "Default")
      (node (ref "IC4") (pin "25") (pinfunction "GPA4_25") (pintype "bidirectional"))
      (node (ref "R57") (pin "1") (pinfunction "1_1") (pintype "passive"))
    )
    (net (code "87") (name "GPA5-1") (class "Default")
      (node (ref "IC1") (pin "26") (pinfunction "GPA5_26") (pintype "bidirectional"))
      (node (ref "R6") (pin "1") (pinfunction "1_1") (pintype "passive"))
    )
    (net (code "88") (name "GPA5-2") (class "Default")
      (node (ref "IC2") (pin "26") (pinfunction "GPA5_26") (pintype "bidirectional"))
      (node (ref "R22") (pin "1") (pinfunction "1_1") (pintype "passive"))
    )
    (net (code "89") (name "GPA5-3") (class "Default")
      (node (ref "IC3") (pin "26") (pinfunction "GPA5_26") (pintype "bidirectional"))
      (node (ref "R38") (pin "1") (pinfunction "1_1") (pintype "passive"))
    )
    (net (code "90") (name "GPA5-4") (class "Default")
      (node (ref "IC4") (pin "26") (pinfunction "GPA5_26") (pintype "bidirectional"))
      (node (ref "R56") (pin "1") (pinfunction "1_1") (pintype "passive"))
    )
    (net (code "91") (name "GPA6-1") (class "Default")
      (node (ref "IC1") (pin "27") (pinfunction "GPA6_27") (pintype "bidirectional"))
      (node (ref "R5") (pin "1") (pinfunction "1_1") (pintype "passive"))
    )
    (net (code "92") (name "GPA6-2") (class "Default")
      (node (ref "IC2") (pin "27") (pinfunction "GPA6_27") (pintype "bidirectional"))
      (node (ref "R21") (pin "1") (pinfunction "1_1") (pintype "passive"))
    )
    (net (code "93") (name "GPA6-3") (class "Default")
      (node (ref "IC3") (pin "27") (pinfunction "GPA6_27") (pintype "bidirectional"))
      (node (ref "R37") (pin "1") (pinfunction "1_1") (pintype "passive"))
    )
    (net (code "94") (name "GPA6-4") (class "Default")
      (node (ref "IC4") (pin "27") (pinfunction "GPA6_27") (pintype "bidirectional"))
      (node (ref "R55") (pin "1") (pinfunction "1_1") (pintype "passive"))
    )
    (net (code "95") (name "GPA7-1") (class "Default")
      (node (ref "IC1") (pin "28") (pinfunction "GPA7_28") (pintype "bidirectional"))
      (node (ref "R8") (pin "1") (pinfunction "1_1") (pintype "passive"))
    )
    (net (code "96") (name "GPA7-2") (class "Default")
      (node (ref "IC2") (pin "28") (pinfunction "GPA7_28") (pintype "bidirectional"))
      (node (ref "R24") (pin "1") (pinfunction "1_1") (pintype "passive"))
    )
    (net (code "97") (name "GPA7-3") (class "Default")
      (node (ref "IC3") (pin "28") (pinfunction "GPA7_28") (pintype "bidirectional"))
      (node (ref "R42") (pin "1") (pinfunction "1_1") (pintype "passive"))
    )
    (net (code "98") (name "GPA7-4") (class "Default")
      (node (ref "IC4") (pin "28") (pinfunction "GPA7_28") (pintype "bidirectional"))
      (node (ref "R58") (pin "1") (pinfunction "1_1") (pintype "passive"))
    )
    (net (code "99") (name "GPB0-1") (class "Default")
      (node (ref "IC1") (pin "1") (pinfunction "GPB0_1") (pintype "bidirectional"))
      (node (ref "R15") (pin "1") (pinfunction "1_1") (pintype "passive"))
    )
    (net (code "100") (name "GPB0-2") (class "Default")
      (node (ref "IC2") (pin "1") (pinfunction "GPB0_1") (pintype "bidirectional"))
      (node (ref "R31") (pin "1") (pinfunction "1_1") (pintype "passive"))
    )
    (net (code "101") (name "GPB0-3") (class "Default")
      (node (ref "IC3") (pin "1") (pinfunction "GPB0_1") (pintype "bidirectional"))
      (node (ref "R49") (pin "1") (pinfunction "1_1") (pintype "passive"))
    )
    (net (code "102") (name "GPB0-4") (class "Default")
      (node (ref "IC4") (pin "1") (pinfunction "GPB0_1") (pintype "bidirectional"))
      (node (ref "R65") (pin "1") (pinfunction "1_1") (pintype "passive"))
    )
    (net (code "103") (name "GPB1-1") (class "Default")
      (node (ref "IC1") (pin "2") (pinfunction "GPB1_2") (pintype "bidirectional"))
      (node (ref "R13") (pin "1") (pinfunction "1_1") (pintype "passive"))
    )
    (net (code "104") (name "GPB1-2") (class "Default")
      (node (ref "IC2") (pin "2") (pinfunction "GPB1_2") (pintype "bidirectional"))
      (node (ref "R29") (pin "1") (pinfunction "1_1") (pintype "passive"))
    )
    (net (code "105") (name "GPB1-3") (class "Default")
      (node (ref "IC3") (pin "2") (pinfunction "GPB1_2") (pintype "bidirectional"))
      (node (ref "R47") (pin "1") (pinfunction "1_1") (pintype "passive"))
    )
    (net (code "106") (name "GPB1-4") (class "Default")
      (node (ref "IC4") (pin "2") (pinfunction "GPB1_2") (pintype "bidirectional"))
      (node (ref "R63") (pin "1") (pinfunction "1_1") (pintype "passive"))
    )
    (net (code "107") (name "GPB2-1") (class "Default")
      (node (ref "IC1") (pin "3") (pinfunction "GPB2_3") (pintype "bidirectional"))
      (node (ref "R11") (pin "1") (pinfunction "1_1") (pintype "passive"))
    )
    (net (code "108") (name "GPB2-2") (class "Default")
      (node (ref "IC2") (pin "3") (pinfunction "GPB2_3") (pintype "bidirectional"))
      (node (ref "R27") (pin "1") (pinfunction "1_1") (pintype "passive"))
    )
    (net (code "109") (name "GPB2-3") (class "Default")
      (node (ref "IC3") (pin "3") (pinfunction "GPB2_3") (pintype "bidirectional"))
      (node (ref "R45") (pin "1") (pinfunction "1_1") (pintype "passive"))
    )
    (net (code "110") (name "GPB2-4") (class "Default")
      (node (ref "IC4") (pin "3") (pinfunction "GPB2_3") (pintype "bidirectional"))
      (node (ref "R61") (pin "1") (pinfunction "1_1") (pintype "passive"))
    )
    (net (code "111") (name "GPB3-1") (class "Default")
      (node (ref "IC1") (pin "4") (pinfunction "GPB3_4") (pintype "bidirectional"))
      (node (ref "R9") (pin "1") (pinfunction "1_1") (pintype "passive"))
    )
    (net (code "112") (name "GPB3-2") (class "Default")
      (node (ref "IC2") (pin "4") (pinfunction "GPB3_4") (pintype "bidirectional"))
      (node (ref "R25") (pin "1") (pinfunction "1_1") (pintype "passive"))
    )
    (net (code "113") (name "GPB3-3") (class "Default")
      (node (ref "IC3") (pin "4") (pinfunction "GPB3_4") (pintype "bidirectional"))
      (node (ref "R43") (pin "1") (pinfunction "1_1") (pintype "passive"))
    )
    (net (code "114") (name "GPB3-4") (class "Default")
      (node (ref "IC4") (pin "4") (pinfunction "GPB3_4") (pintype "bidirectional"))
      (node (ref "R59") (pin "1") (pinfunction "1_1") (pintype "passive"))
    )
    (net (code "115") (name "GPB4-1") (class "Default")
      (node (ref "IC1") (pin "5") (pinfunction "GPB4_5") (pintype "bidirectional"))
      (node (ref "R16") (pin "1") (pinfunction "1_1") (pintype "passive"))
    )
    (net (code "116") (name "GPB4-2") (class "Default")
      (node (ref "IC2") (pin "5") (pinfunction "GPB4_5") (pintype "bidirectional"))
      (node (ref "R32") (pin "1") (pinfunction "1_1") (pintype "passive"))
    )
    (net (code "117") (name "GPB4-3") (class "Default")
      (node (ref "IC3") (pin "5") (pinfunction "GPB4_5") (pintype "bidirectional"))
      (node (ref "R50") (pin "1") (pinfunction "1_1") (pintype "passive"))
    )
    (net (code "118") (name "GPB4-4") (class "Default")
      (node (ref "IC4") (pin "5") (pinfunction "GPB4_5") (pintype "bidirectional"))
      (node (ref "R66") (pin "1") (pinfunction "1_1") (pintype "passive"))
    )
    (net (code "119") (name "GPB5-1") (class "Default")
      (node (ref "IC1") (pin "6") (pinfunction "GPB5_6") (pintype "bidirectional"))
      (node (ref "R14") (pin "1") (pinfunction "1_1") (pintype "passive"))
    )
    (net (code "120") (name "GPB5-2") (class "Default")
      (node (ref "IC2") (pin "6") (pinfunction "GPB5_6") (pintype "bidirectional"))
      (node (ref "R30") (pin "1") (pinfunction "1_1") (pintype "passive"))
    )
    (net (code "121") (name "GPB5-3") (class "Default")
      (node (ref "IC3") (pin "6") (pinfunction "GPB5_6") (pintype "bidirectional"))
      (node (ref "R48") (pin "1") (pinfunction "1_1") (pintype "passive"))
    )
    (net (code "122") (name "GPB5-4") (class "Default")
      (node (ref "IC4") (pin "6") (pinfunction "GPB5_6") (pintype "bidirectional"))
      (node (ref "R64") (pin "1") (pinfunction "1_1") (pintype "passive"))
    )
    (net (code "123") (name "GPB6-1") (class "Default")
      (node (ref "IC1") (pin "7") (pinfunction "GPB6_7") (pintype "bidirectional"))
      (node (ref "R12") (pin "1") (pinfunction "1_1") (pintype "passive"))
    )
    (net (code "124") (name "GPB6-2") (class "Default")
      (node (ref "IC2") (pin "7") (pinfunction "GPB6_7") (pintype "bidirectional"))
      (node (ref "R28") (pin "1") (pinfunction "1_1") (pintype "passive"))
    )
    (net (code "125") (name "GPB6-3") (class "Default")
      (node (ref "IC3") (pin "7") (pinfunction "GPB6_7") (pintype "bidirectional"))
      (node (ref "R46") (pin "1") (pinfunction "1_1") (pintype "passive"))
    )
    (net (code "126") (name "GPB6-4") (class "Default")
      (node (ref "IC4") (pin "7") (pinfunction "GPB6_7") (pintype "bidirectional"))
      (node (ref "R62") (pin "1") (pinfunction "1_1") (pintype "passive"))
    )
    (net (code "127") (name "GPB7-1") (class "Default")
      (node (ref "IC1") (pin "8") (pinfunction "GPB7_8") (pintype "bidirectional"))
      (node (ref "R10") (pin "1") (pinfunction "1_1") (pintype "passive"))
    )
    (net (code "128") (name "GPB7-2") (class "Default")
      (node (ref "IC2") (pin "8") (pinfunction "GPB7_8") (pintype "bidirectional"))
      (node (ref "R26") (pin "1") (pinfunction "1_1") (pintype "passive"))
    )
    (net (code "129") (name "GPB7-3") (class "Default")
      (node (ref "IC3") (pin "8") (pinfunction "GPB7_8") (pintype "bidirectional"))
      (node (ref "R44") (pin "1") (pinfunction "1_1") (pintype "passive"))
    )
    (net (code "130") (name "GPB7-4") (class "Default")
      (node (ref "IC4") (pin "8") (pinfunction "GPB7_8") (pintype "bidirectional"))
      (node (ref "R60") (pin "1") (pinfunction "1_1") (pintype "passive"))
    )
    (net (code "131") (name "Net-(LED1-PadA)") (class "Default")
      (node (ref "LED1") (pin "A") (pinfunction "A_A") (pintype "passive"))
      (node (ref "R39") (pin "1") (pinfunction "1_1") (pintype "passive"))
    )
    (net (code "132") (name "Net-(LED2-PadA)") (class "Default")
      (node (ref "LED2") (pin "A") (pinfunction "A_A") (pintype "passive"))
      (node (ref "R40") (pin "1") (pinfunction "1_1") (pintype "passive"))
    )
    (net (code "133") (name "Net-(R68-Pad2)") (class "Default")
      (node (ref "R68") (pin "2") (pinfunction "2_2") (pintype "passive"))
      (node (ref "SJ2") (pin "1") (pinfunction "1_1") (pintype "passive"))
    )
    (net (code "134") (name "Net-(R69-Pad2)") (class "Default")
      (node (ref "R69") (pin "2") (pinfunction "2_2") (pintype "passive"))
      (node (ref "SJ3") (pin "1") (pinfunction "1_1") (pintype "passive"))
    )
    (net (code "135") (name "SCL") (class "Default")
      (node (ref "IC1") (pin "12") (pinfunction "SCL_12") (pintype "input"))
      (node (ref "IC2") (pin "12") (pinfunction "SCL_12") (pintype "input"))
      (node (ref "IC3") (pin "12") (pinfunction "SCL_12") (pintype "input"))
      (node (ref "IC4") (pin "12") (pinfunction "SCL_12") (pintype "input"))
      (node (ref "J3") (pin "2") (pinfunction "2_2") (pintype "passive"))
      (node (ref "R68") (pin "1") (pinfunction "1_1") (pintype "passive"))
    )
    (net (code "136") (name "SDA") (class "Default")
      (node (ref "IC1") (pin "13") (pinfunction "SDA_13") (pintype "bidirectional"))
      (node (ref "IC2") (pin "13") (pinfunction "SDA_13") (pintype "bidirectional"))
      (node (ref "IC3") (pin "13") (pinfunction "SDA_13") (pintype "bidirectional"))
      (node (ref "IC4") (pin "13") (pinfunction "SDA_13") (pintype "bidirectional"))
      (node (ref "J3") (pin "1") (pinfunction "1_1") (pintype "passive"))
      (node (ref "R69") (pin "1") (pinfunction "1_1") (pintype "passive"))
    )
    (net (code "137") (name "VCC") (class "Default")
      (node (ref "C1") (pin "1") (pinfunction "1_1") (pintype "passive"))
      (node (ref "C2") (pin "1") (pinfunction "1_1") (pintype "passive"))
      (node (ref "C3") (pin "1") (pinfunction "1_1") (pintype "passive"))
      (node (ref "C4") (pin "1") (pinfunction "1_1") (pintype "passive"))
      (node (ref "IC1") (pin "18") (pinfunction "~{RESET}_18") (pintype "input"))
      (node (ref "IC1") (pin "9") (pinfunction "VDD_9") (pintype "power_in"))
      (node (ref "IC2") (pin "15") (pinfunction "A0_15") (pintype "input"))
      (node (ref "IC2") (pin "18") (pinfunction "~{RESET}_18") (pintype "input"))
      (node (ref "IC2") (pin "9") (pinfunction "VDD_9") (pintype "power_in"))
      (node (ref "IC3") (pin "16") (pinfunction "A1_16") (pintype "input"))
      (node (ref "IC3") (pin "18") (pinfunction "~{RESET}_18") (pintype "input"))
      (node (ref "IC3") (pin "9") (pinfunction "VDD_9") (pintype "power_in"))
      (node (ref "IC4") (pin "15") (pinfunction "A0_15") (pintype "input"))
      (node (ref "IC4") (pin "16") (pinfunction "A1_16") (pintype "input"))
      (node (ref "IC4") (pin "18") (pinfunction "~{RESET}_18") (pintype "input"))
      (node (ref "IC4") (pin "9") (pinfunction "VDD_9") (pintype "power_in"))
      (node (ref "J3") (pin "3") (pinfunction "3_3") (pintype "passive"))
      (node (ref "R39") (pin "2") (pinfunction "2_2") (pintype "passive"))
      (node (ref "SJ1") (pin "2") (pinfunction "2_2") (pintype "passive"))
      (node (ref "SJ2") (pin "2") (pinfunction "2_2") (pintype "passive"))
      (node (ref "SJ3") (pin "2") (pinfunction "2_2") (pintype "passive"))
    )
    (net (code "138") (name "VIN") (class "Default")
      (node (ref "C7") (pin "+") (pinfunction "+_+") (pintype "passive"))
      (node (ref "J1") (pin "A4") (pinfunction "A4_A4") (pintype "bidirectional"))
      (node (ref "J1") (pin "A5") (pinfunction "A5_A5") (pintype "bidirectional"))
      (node (ref "J1") (pin "B4") (pinfunction "B4_B4") (pintype "bidirectional"))
      (node (ref "J1") (pin "B5") (pinfunction "B5_B5") (pintype "bidirectional"))
      (node (ref "J1") (pin "C4") (pinfunction "C4_C4") (pintype "bidirectional"))
      (node (ref "J1") (pin "C5") (pinfunction "C5_C5") (pintype "bidirectional"))
      (node (ref "J1") (pin "D4") (pinfunction "D4_D4") (pintype "bidirectional"))
      (node (ref "J1") (pin "D5") (pinfunction "D5_D5") (pintype "bidirectional"))
      (node (ref "J1") (pin "E4") (pinfunction "E4_E4") (pintype "bidirectional"))
      (node (ref "J1") (pin "E5") (pinfunction "E5_E5") (pintype "bidirectional"))
      (node (ref "J1") (pin "F4") (pinfunction "F4_F4") (pintype "bidirectional"))
      (node (ref "J1") (pin "F5") (pinfunction "F5_F5") (pintype "bidirectional"))
      (node (ref "J1") (pin "G4") (pinfunction "G4_G4") (pintype "bidirectional"))
      (node (ref "J1") (pin "G5") (pinfunction "G5_G5") (pintype "bidirectional"))
      (node (ref "J1") (pin "H4") (pinfunction "H4_H4") (pintype "bidirectional"))
      (node (ref "J1") (pin "H5") (pinfunction "H5_H5") (pintype "bidirectional"))
      (node (ref "J2") (pin "A4") (pinfunction "A4_A4") (pintype "bidirectional"))
      (node (ref "J2") (pin "A5") (pinfunction "A5_A5") (pintype "bidirectional"))
      (node (ref "J2") (pin "B4") (pinfunction "B4_B4") (pintype "bidirectional"))
      (node (ref "J2") (pin "B5") (pinfunction "B5_B5") (pintype "bidirectional"))
      (node (ref "J2") (pin "C4") (pinfunction "C4_C4") (pintype "bidirectional"))
      (node (ref "J2") (pin "C5") (pinfunction "C5_C5") (pintype "bidirectional"))
      (node (ref "J2") (pin "D4") (pinfunction "D4_D4") (pintype "bidirectional"))
      (node (ref "J2") (pin "D5") (pinfunction "D5_D5") (pintype "bidirectional"))
      (node (ref "J2") (pin "E4") (pinfunction "E4_E4") (pintype "bidirectional"))
      (node (ref "J2") (pin "E5") (pinfunction "E5_E5") (pintype "bidirectional"))
      (node (ref "J2") (pin "F4") (pinfunction "F4_F4") (pintype "bidirectional"))
      (node (ref "J2") (pin "F5") (pinfunction "F5_F5") (pintype "bidirectional"))
      (node (ref "J2") (pin "G4") (pinfunction "G4_G4") (pintype "bidirectional"))
      (node (ref "J2") (pin "G5") (pinfunction "G5_G5") (pintype "bidirectional"))
      (node (ref "J2") (pin "H4") (pinfunction "H4_H4") (pintype "bidirectional"))
      (node (ref "J2") (pin "H5") (pinfunction "H5_H5") (pintype "bidirectional"))
      (node (ref "J3") (pin "5") (pinfunction "5_5") (pintype "passive"))
      (node (ref "R40") (pin "2") (pinfunction "2_2") (pintype "passive"))
    )
    (net (code "139") (name "unconnected-(IC1-INTB-Pad19)") (class "Default")
      (node (ref "IC1") (pin "19") (pinfunction "INTB_19") (pintype "output"))
    )
    (net (code "140") (name "unconnected-(IC2-INTB-Pad19)") (class "Default")
      (node (ref "IC2") (pin "19") (pinfunction "INTB_19") (pintype "output"))
    )
    (net (code "141") (name "unconnected-(IC3-INTB-Pad19)") (class "Default")
      (node (ref "IC3") (pin "19") (pinfunction "INTB_19") (pintype "output"))
    )
    (net (code "142") (name "unconnected-(IC4-INTB-Pad19)") (class "Default")
      (node (ref "IC4") (pin "19") (pinfunction "INTB_19") (pintype "output"))
    )
    (net (code "143") (name "~{INT}") (class "Default")
      (node (ref "IC1") (pin "20") (pinfunction "INTA_20") (pintype "output"))
      (node (ref "IC2") (pin "20") (pinfunction "INTA_20") (pintype "output"))
      (node (ref "IC3") (pin "20") (pinfunction "INTA_20") (pintype "output"))
      (node (ref "IC4") (pin "20") (pinfunction "INTA_20") (pintype "output"))
      (node (ref "J3") (pin "6") (pinfunction "6_6") (pintype "passive"))
    )
  )
)
